# Nutrient_Management_Control.net
KiCad netlist of a schematic drawn in EAGLE
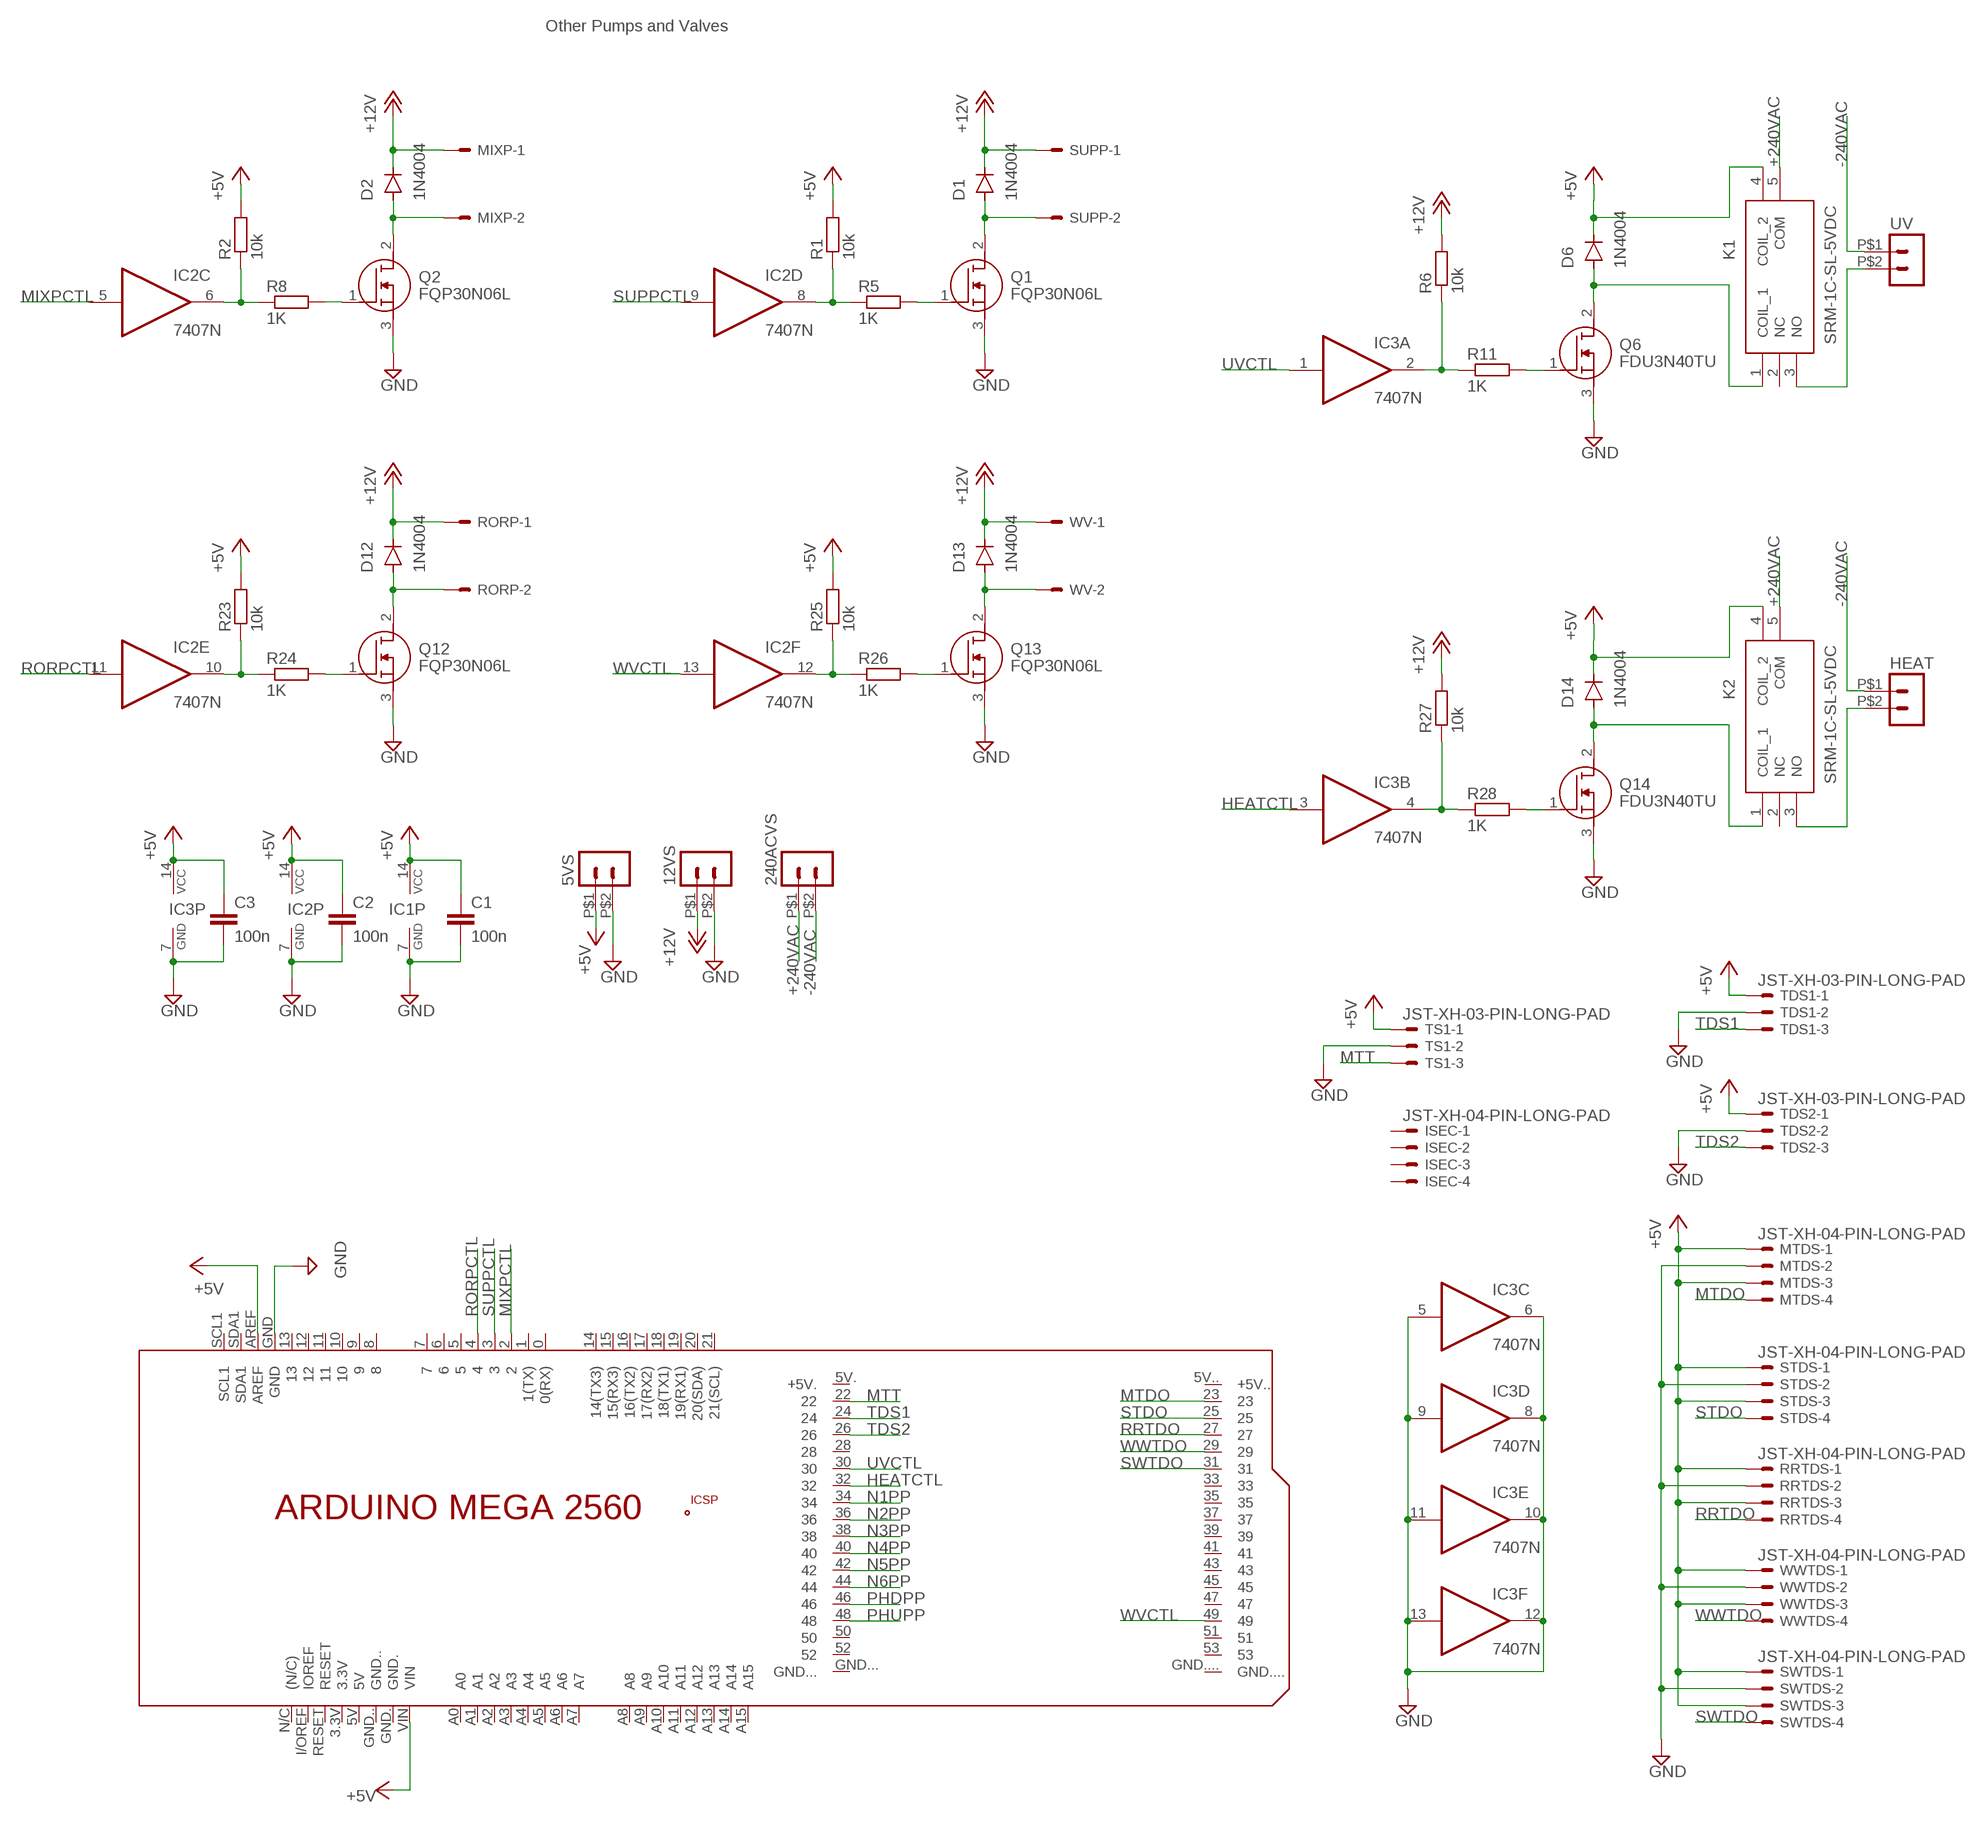
[diagram p0: schematic, sheet 1, part 1 of 2]
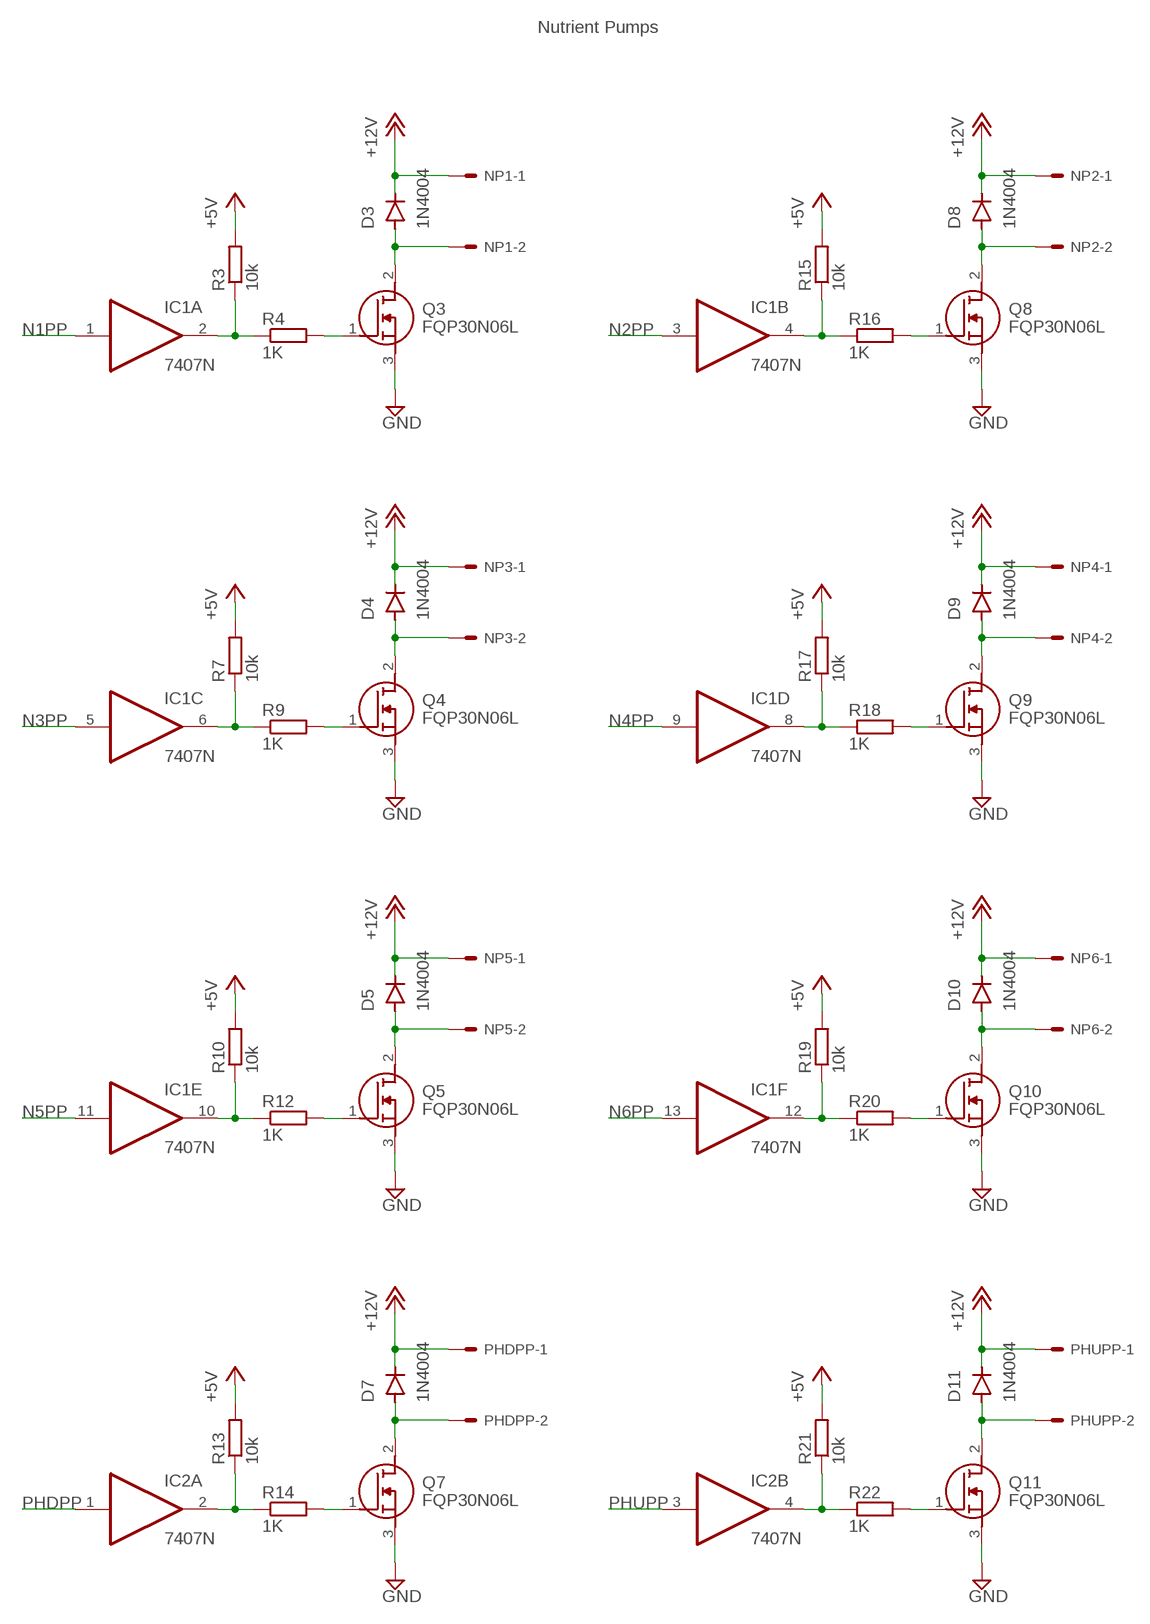
[diagram p1: schematic, sheet 1, part 2 of 2]

(export (version "E")
  (design (tool "Eeschema 10.0.6"))
  (components
    (comp (ref "5VS")
      (value "HEADER_POS2_43650-0215")
      (footprint "eagle-import:43650-0215")
      (libsource (lib "eagle-import") (part "HEADER_POS2_?43650-0215"))
    )
    (comp (ref "12VS")
      (value "HEADER_POS2_43650-0215")
      (footprint "eagle-import:43650-0215")
      (libsource (lib "eagle-import") (part "HEADER_POS2_?43650-0215"))
    )
    (comp (ref "240ACVS")
      (value "HEADER_POS2_43650-0215")
      (footprint "eagle-import:43650-0215")
      (libsource (lib "eagle-import") (part "HEADER_POS2_?43650-0215"))
    )
    (comp (ref "C1")
      (value "100n")
      (footprint "eagle-import:C050-024X044")
      (libsource (lib "eagle-import") (part "C-EU050-024X044"))
    )
    (comp (ref "C2")
      (value "100n")
      (footprint "eagle-import:C050-024X044")
      (libsource (lib "eagle-import") (part "C-EU050-024X044"))
    )
    (comp (ref "C3")
      (value "100n")
      (footprint "eagle-import:C050-024X044")
      (libsource (lib "eagle-import") (part "C-EU050-024X044"))
    )
    (comp (ref "D1")
      (value "1N4004")
      (footprint "eagle-import:DO-41")
      (fields
        (field (name "DIGIKEY_PART_NUMBER") "1N4004MSCT-ND")
        (field (name "MANUFACTURER") "Micro Commercial Co")
        (field (name "CREATED_BY") "PCBLayout.com")
      )
      (libsource (lib "eagle-import") (part "1N4004"))
    )
    (comp (ref "D2")
      (value "1N4004")
      (footprint "eagle-import:DO-41")
      (fields
        (field (name "DIGIKEY_PART_NUMBER") "1N4004MSCT-ND")
        (field (name "MANUFACTURER") "Micro Commercial Co")
        (field (name "CREATED_BY") "PCBLayout.com")
      )
      (libsource (lib "eagle-import") (part "1N4004"))
    )
    (comp (ref "D3")
      (value "1N4004")
      (footprint "eagle-import:DO-41")
      (fields
        (field (name "DIGIKEY_PART_NUMBER") "1N4004MSCT-ND")
        (field (name "MANUFACTURER") "Micro Commercial Co")
        (field (name "CREATED_BY") "PCBLayout.com")
      )
      (libsource (lib "eagle-import") (part "1N4004"))
    )
    (comp (ref "D4")
      (value "1N4004")
      (footprint "eagle-import:DO-41")
      (fields
        (field (name "DIGIKEY_PART_NUMBER") "1N4004MSCT-ND")
        (field (name "MANUFACTURER") "Micro Commercial Co")
        (field (name "CREATED_BY") "PCBLayout.com")
      )
      (libsource (lib "eagle-import") (part "1N4004"))
    )
    (comp (ref "D5")
      (value "1N4004")
      (footprint "eagle-import:DO-41")
      (fields
        (field (name "DIGIKEY_PART_NUMBER") "1N4004MSCT-ND")
        (field (name "MANUFACTURER") "Micro Commercial Co")
        (field (name "CREATED_BY") "PCBLayout.com")
      )
      (libsource (lib "eagle-import") (part "1N4004"))
    )
    (comp (ref "D6")
      (value "1N4004")
      (footprint "eagle-import:DO-41")
      (fields
        (field (name "DIGIKEY_PART_NUMBER") "1N4004MSCT-ND")
        (field (name "MANUFACTURER") "Micro Commercial Co")
        (field (name "CREATED_BY") "PCBLayout.com")
      )
      (libsource (lib "eagle-import") (part "1N4004"))
    )
    (comp (ref "D7")
      (value "1N4004")
      (footprint "eagle-import:DO-41")
      (fields
        (field (name "DIGIKEY_PART_NUMBER") "1N4004MSCT-ND")
        (field (name "MANUFACTURER") "Micro Commercial Co")
        (field (name "CREATED_BY") "PCBLayout.com")
      )
      (libsource (lib "eagle-import") (part "1N4004"))
    )
    (comp (ref "D8")
      (value "1N4004")
      (footprint "eagle-import:DO-41")
      (fields
        (field (name "DIGIKEY_PART_NUMBER") "1N4004MSCT-ND")
        (field (name "MANUFACTURER") "Micro Commercial Co")
        (field (name "CREATED_BY") "PCBLayout.com")
      )
      (libsource (lib "eagle-import") (part "1N4004"))
    )
    (comp (ref "D9")
      (value "1N4004")
      (footprint "eagle-import:DO-41")
      (fields
        (field (name "DIGIKEY_PART_NUMBER") "1N4004MSCT-ND")
        (field (name "MANUFACTURER") "Micro Commercial Co")
        (field (name "CREATED_BY") "PCBLayout.com")
      )
      (libsource (lib "eagle-import") (part "1N4004"))
    )
    (comp (ref "D10")
      (value "1N4004")
      (footprint "eagle-import:DO-41")
      (fields
        (field (name "DIGIKEY_PART_NUMBER") "1N4004MSCT-ND")
        (field (name "MANUFACTURER") "Micro Commercial Co")
        (field (name "CREATED_BY") "PCBLayout.com")
      )
      (libsource (lib "eagle-import") (part "1N4004"))
    )
    (comp (ref "D11")
      (value "1N4004")
      (footprint "eagle-import:DO-41")
      (fields
        (field (name "DIGIKEY_PART_NUMBER") "1N4004MSCT-ND")
        (field (name "MANUFACTURER") "Micro Commercial Co")
        (field (name "CREATED_BY") "PCBLayout.com")
      )
      (libsource (lib "eagle-import") (part "1N4004"))
    )
    (comp (ref "D12")
      (value "1N4004")
      (footprint "eagle-import:DO-41")
      (fields
        (field (name "DIGIKEY_PART_NUMBER") "1N4004MSCT-ND")
        (field (name "MANUFACTURER") "Micro Commercial Co")
        (field (name "CREATED_BY") "PCBLayout.com")
      )
      (libsource (lib "eagle-import") (part "1N4004"))
    )
    (comp (ref "D13")
      (value "1N4004")
      (footprint "eagle-import:DO-41")
      (fields
        (field (name "DIGIKEY_PART_NUMBER") "1N4004MSCT-ND")
        (field (name "MANUFACTURER") "Micro Commercial Co")
        (field (name "CREATED_BY") "PCBLayout.com")
      )
      (libsource (lib "eagle-import") (part "1N4004"))
    )
    (comp (ref "D14")
      (value "1N4004")
      (footprint "eagle-import:DO-41")
      (fields
        (field (name "DIGIKEY_PART_NUMBER") "1N4004MSCT-ND")
        (field (name "MANUFACTURER") "Micro Commercial Co")
        (field (name "CREATED_BY") "PCBLayout.com")
      )
      (libsource (lib "eagle-import") (part "1N4004"))
    )
    (comp (ref "HEAT")
      (value "HEADER_POS2_43650-0215")
      (footprint "eagle-import:43650-0215")
      (libsource (lib "eagle-import") (part "HEADER_POS2_?43650-0215"))
    )
    (comp (ref "IC1")
      (value "7407N")
      (footprint "eagle-import:DIL14")
      (libsource (lib "eagle-import") (part "7407N"))
    )
    (comp (ref "IC2")
      (value "7407N")
      (footprint "eagle-import:DIL14")
      (libsource (lib "eagle-import") (part "7407N"))
    )
    (comp (ref "IC3")
      (value "7407N")
      (footprint "eagle-import:DIL14")
      (libsource (lib "eagle-import") (part "7407N"))
    )
    (comp (ref "ISEC")
      (value "JST-XH-04-PIN-LONG-PAD")
      (footprint "eagle-import:JST-XH-04-PACKAGE-LONG-PAD")
      (libsource (lib "eagle-import") (part "JST-XH-04-PIN-LONG-PAD"))
    )
    (comp (ref "K1")
      (value "SRM-1C-SL-5VDC")
      (footprint "eagle-import:SRM1CSL5VDC")
      (libsource (lib "eagle-import") (part "SRM-1C-SL-5VDC"))
    )
    (comp (ref "K2")
      (value "SRM-1C-SL-5VDC")
      (footprint "eagle-import:SRM1CSL5VDC")
      (libsource (lib "eagle-import") (part "SRM-1C-SL-5VDC"))
    )
    (comp (ref "MIXP")
      (value "JST-XH-02-PIN-LONG-PAD")
      (footprint "eagle-import:JST-XH-02-PACKAGE-LONG-PAD")
      (libsource (lib "eagle-import") (part "JST-XH-02-PIN-LONG-PAD"))
    )
    (comp (ref "MTDS")
      (value "JST-XH-04-PIN-LONG-PAD")
      (footprint "eagle-import:JST-XH-04-PACKAGE-LONG-PAD")
      (libsource (lib "eagle-import") (part "JST-XH-04-PIN-LONG-PAD"))
    )
    (comp (ref "NP1")
      (value "JST-XH-02-PIN-LONG-PAD")
      (footprint "eagle-import:JST-XH-02-PACKAGE-LONG-PAD")
      (libsource (lib "eagle-import") (part "JST-XH-02-PIN-LONG-PAD"))
    )
    (comp (ref "NP2")
      (value "JST-XH-02-PIN-LONG-PAD")
      (footprint "eagle-import:JST-XH-02-PACKAGE-LONG-PAD")
      (libsource (lib "eagle-import") (part "JST-XH-02-PIN-LONG-PAD"))
    )
    (comp (ref "NP3")
      (value "JST-XH-02-PIN-LONG-PAD")
      (footprint "eagle-import:JST-XH-02-PACKAGE-LONG-PAD")
      (libsource (lib "eagle-import") (part "JST-XH-02-PIN-LONG-PAD"))
    )
    (comp (ref "NP4")
      (value "JST-XH-02-PIN-LONG-PAD")
      (footprint "eagle-import:JST-XH-02-PACKAGE-LONG-PAD")
      (libsource (lib "eagle-import") (part "JST-XH-02-PIN-LONG-PAD"))
    )
    (comp (ref "NP5")
      (value "JST-XH-02-PIN-LONG-PAD")
      (footprint "eagle-import:JST-XH-02-PACKAGE-LONG-PAD")
      (libsource (lib "eagle-import") (part "JST-XH-02-PIN-LONG-PAD"))
    )
    (comp (ref "NP6")
      (value "JST-XH-02-PIN-LONG-PAD")
      (footprint "eagle-import:JST-XH-02-PACKAGE-LONG-PAD")
      (libsource (lib "eagle-import") (part "JST-XH-02-PIN-LONG-PAD"))
    )
    (comp (ref "PCB2")
      (value "ARDUINO_MEGA2560_SHIELD")
      (footprint "eagle-import:ARDUINO_MEGA2560_SHIELD")
      (libsource (lib "eagle-import") (part "ARDUINO_MEGA2560_SHIELD"))
    )
    (comp (ref "PHDPP")
      (value "JST-XH-02-PIN-LONG-PAD")
      (footprint "eagle-import:JST-XH-02-PACKAGE-LONG-PAD")
      (libsource (lib "eagle-import") (part "JST-XH-02-PIN-LONG-PAD"))
    )
    (comp (ref "PHUPP")
      (value "JST-XH-02-PIN-LONG-PAD")
      (footprint "eagle-import:JST-XH-02-PACKAGE-LONG-PAD")
      (libsource (lib "eagle-import") (part "JST-XH-02-PIN-LONG-PAD"))
    )
    (comp (ref "Q1")
      (value "FQP30N06L")
      (footprint "eagle-import:TO254P470X1016X2019-3P")
      (fields (field (name "RS_PART_NUMBER") "8075863P"))
      (libsource (lib "eagle-import") (part "FQP30N06L"))
    )
    (comp (ref "Q2")
      (value "FQP30N06L")
      (footprint "eagle-import:TO254P470X1016X2019-3P")
      (fields (field (name "RS_PART_NUMBER") "8075863P"))
      (libsource (lib "eagle-import") (part "FQP30N06L"))
    )
    (comp (ref "Q3")
      (value "FQP30N06L")
      (footprint "eagle-import:TO254P470X1016X2019-3P")
      (fields (field (name "RS_PART_NUMBER") "8075863P"))
      (libsource (lib "eagle-import") (part "FQP30N06L"))
    )
    (comp (ref "Q4")
      (value "FQP30N06L")
      (footprint "eagle-import:TO254P470X1016X2019-3P")
      (fields (field (name "RS_PART_NUMBER") "8075863P"))
      (libsource (lib "eagle-import") (part "FQP30N06L"))
    )
    (comp (ref "Q5")
      (value "FQP30N06L")
      (footprint "eagle-import:TO254P470X1016X2019-3P")
      (fields (field (name "RS_PART_NUMBER") "8075863P"))
      (libsource (lib "eagle-import") (part "FQP30N06L"))
    )
    (comp (ref "Q6")
      (value "FDU3N40TU")
      (footprint "eagle-import:TO229P250X658X985-3P")
      (fields (field (name "RS_PART_NUMBER") "8070701P"))
      (libsource (lib "eagle-import") (part "FDU3N40TU"))
    )
    (comp (ref "Q7")
      (value "FQP30N06L")
      (footprint "eagle-import:TO254P470X1016X2019-3P")
      (fields (field (name "RS_PART_NUMBER") "8075863P"))
      (libsource (lib "eagle-import") (part "FQP30N06L"))
    )
    (comp (ref "Q8")
      (value "FQP30N06L")
      (footprint "eagle-import:TO254P470X1016X2019-3P")
      (fields (field (name "RS_PART_NUMBER") "8075863P"))
      (libsource (lib "eagle-import") (part "FQP30N06L"))
    )
    (comp (ref "Q9")
      (value "FQP30N06L")
      (footprint "eagle-import:TO254P470X1016X2019-3P")
      (fields (field (name "RS_PART_NUMBER") "8075863P"))
      (libsource (lib "eagle-import") (part "FQP30N06L"))
    )
    (comp (ref "Q10")
      (value "FQP30N06L")
      (footprint "eagle-import:TO254P470X1016X2019-3P")
      (fields (field (name "RS_PART_NUMBER") "8075863P"))
      (libsource (lib "eagle-import") (part "FQP30N06L"))
    )
    (comp (ref "Q11")
      (value "FQP30N06L")
      (footprint "eagle-import:TO254P470X1016X2019-3P")
      (fields (field (name "RS_PART_NUMBER") "8075863P"))
      (libsource (lib "eagle-import") (part "FQP30N06L"))
    )
    (comp (ref "Q12")
      (value "FQP30N06L")
      (footprint "eagle-import:TO254P470X1016X2019-3P")
      (fields (field (name "RS_PART_NUMBER") "8075863P"))
      (libsource (lib "eagle-import") (part "FQP30N06L"))
    )
    (comp (ref "Q13")
      (value "FQP30N06L")
      (footprint "eagle-import:TO254P470X1016X2019-3P")
      (fields (field (name "RS_PART_NUMBER") "8075863P"))
      (libsource (lib "eagle-import") (part "FQP30N06L"))
    )
    (comp (ref "Q14")
      (value "FDU3N40TU")
      (footprint "eagle-import:TO229P250X658X985-3P")
      (fields (field (name "RS_PART_NUMBER") "8070701P"))
      (libsource (lib "eagle-import") (part "FDU3N40TU"))
    )
    (comp (ref "R1")
      (value "10k")
      (footprint "eagle-import:0204_7")
      (libsource (lib "eagle-import") (part "R-EU_0204/7"))
    )
    (comp (ref "R2")
      (value "10k")
      (footprint "eagle-import:0204_7")
      (libsource (lib "eagle-import") (part "R-EU_0204/7"))
    )
    (comp (ref "R3")
      (value "10k")
      (footprint "eagle-import:0204_7")
      (libsource (lib "eagle-import") (part "R-EU_0204/7"))
    )
    (comp (ref "R4")
      (value "1K")
      (footprint "eagle-import:0204_7")
      (libsource (lib "eagle-import") (part "R-EU_0204/7"))
    )
    (comp (ref "R5")
      (value "1K")
      (footprint "eagle-import:0204_7")
      (libsource (lib "eagle-import") (part "R-EU_0204/7"))
    )
    (comp (ref "R6")
      (value "10k")
      (footprint "eagle-import:0204_7")
      (libsource (lib "eagle-import") (part "R-EU_0204/7"))
    )
    (comp (ref "R7")
      (value "10k")
      (footprint "eagle-import:0204_7")
      (libsource (lib "eagle-import") (part "R-EU_0204/7"))
    )
    (comp (ref "R8")
      (value "1K")
      (footprint "eagle-import:0204_7")
      (libsource (lib "eagle-import") (part "R-EU_0204/7"))
    )
    (comp (ref "R9")
      (value "1K")
      (footprint "eagle-import:0204_7")
      (libsource (lib "eagle-import") (part "R-EU_0204/7"))
    )
    (comp (ref "R10")
      (value "10k")
      (footprint "eagle-import:0204_7")
      (libsource (lib "eagle-import") (part "R-EU_0204/7"))
    )
    (comp (ref "R11")
      (value "1K")
      (footprint "eagle-import:0204_7")
      (libsource (lib "eagle-import") (part "R-EU_0204/7"))
    )
    (comp (ref "R12")
      (value "1K")
      (footprint "eagle-import:0204_7")
      (libsource (lib "eagle-import") (part "R-EU_0204/7"))
    )
    (comp (ref "R13")
      (value "10k")
      (footprint "eagle-import:0204_7")
      (libsource (lib "eagle-import") (part "R-EU_0204/7"))
    )
    (comp (ref "R14")
      (value "1K")
      (footprint "eagle-import:0204_7")
      (libsource (lib "eagle-import") (part "R-EU_0204/7"))
    )
    (comp (ref "R15")
      (value "10k")
      (footprint "eagle-import:0204_7")
      (libsource (lib "eagle-import") (part "R-EU_0204/7"))
    )
    (comp (ref "R16")
      (value "1K")
      (footprint "eagle-import:0204_7")
      (libsource (lib "eagle-import") (part "R-EU_0204/7"))
    )
    (comp (ref "R17")
      (value "10k")
      (footprint "eagle-import:0204_7")
      (libsource (lib "eagle-import") (part "R-EU_0204/7"))
    )
    (comp (ref "R18")
      (value "1K")
      (footprint "eagle-import:0204_7")
      (libsource (lib "eagle-import") (part "R-EU_0204/7"))
    )
    (comp (ref "R19")
      (value "10k")
      (footprint "eagle-import:0204_7")
      (libsource (lib "eagle-import") (part "R-EU_0204/7"))
    )
    (comp (ref "R20")
      (value "1K")
      (footprint "eagle-import:0204_7")
      (libsource (lib "eagle-import") (part "R-EU_0204/7"))
    )
    (comp (ref "R21")
      (value "10k")
      (footprint "eagle-import:0204_7")
      (libsource (lib "eagle-import") (part "R-EU_0204/7"))
    )
    (comp (ref "R22")
      (value "1K")
      (footprint "eagle-import:0204_7")
      (libsource (lib "eagle-import") (part "R-EU_0204/7"))
    )
    (comp (ref "R23")
      (value "10k")
      (footprint "eagle-import:0204_7")
      (libsource (lib "eagle-import") (part "R-EU_0204/7"))
    )
    (comp (ref "R24")
      (value "1K")
      (footprint "eagle-import:0204_7")
      (libsource (lib "eagle-import") (part "R-EU_0204/7"))
    )
    (comp (ref "R25")
      (value "10k")
      (footprint "eagle-import:0204_7")
      (libsource (lib "eagle-import") (part "R-EU_0204/7"))
    )
    (comp (ref "R26")
      (value "1K")
      (footprint "eagle-import:0204_7")
      (libsource (lib "eagle-import") (part "R-EU_0204/7"))
    )
    (comp (ref "R27")
      (value "10k")
      (footprint "eagle-import:0204_7")
      (libsource (lib "eagle-import") (part "R-EU_0204/7"))
    )
    (comp (ref "R28")
      (value "1K")
      (footprint "eagle-import:0204_7")
      (libsource (lib "eagle-import") (part "R-EU_0204/7"))
    )
    (comp (ref "RORP")
      (value "JST-XH-02-PIN-LONG-PAD")
      (footprint "eagle-import:JST-XH-02-PACKAGE-LONG-PAD")
      (libsource (lib "eagle-import") (part "JST-XH-02-PIN-LONG-PAD"))
    )
    (comp (ref "RRTDS")
      (value "JST-XH-04-PIN-LONG-PAD")
      (footprint "eagle-import:JST-XH-04-PACKAGE-LONG-PAD")
      (libsource (lib "eagle-import") (part "JST-XH-04-PIN-LONG-PAD"))
    )
    (comp (ref "STDS")
      (value "JST-XH-04-PIN-LONG-PAD")
      (footprint "eagle-import:JST-XH-04-PACKAGE-LONG-PAD")
      (libsource (lib "eagle-import") (part "JST-XH-04-PIN-LONG-PAD"))
    )
    (comp (ref "SUPP")
      (value "JST-XH-02-PIN-LONG-PAD")
      (footprint "eagle-import:JST-XH-02-PACKAGE-LONG-PAD")
      (libsource (lib "eagle-import") (part "JST-XH-02-PIN-LONG-PAD"))
    )
    (comp (ref "SWTDS")
      (value "JST-XH-04-PIN-LONG-PAD")
      (footprint "eagle-import:JST-XH-04-PACKAGE-LONG-PAD")
      (libsource (lib "eagle-import") (part "JST-XH-04-PIN-LONG-PAD"))
    )
    (comp (ref "TDS1")
      (value "JST-XH-03-PIN-LONG-PAD")
      (footprint "eagle-import:JST-XH-03-PACKAGE-LONG-PAD")
      (libsource (lib "eagle-import") (part "JST-XH-03-PIN-LONG-PAD"))
    )
    (comp (ref "TDS2")
      (value "JST-XH-03-PIN-LONG-PAD")
      (footprint "eagle-import:JST-XH-03-PACKAGE-LONG-PAD")
      (libsource (lib "eagle-import") (part "JST-XH-03-PIN-LONG-PAD"))
    )
    (comp (ref "TS1")
      (value "JST-XH-03-PIN-LONG-PAD")
      (footprint "eagle-import:JST-XH-03-PACKAGE-LONG-PAD")
      (libsource (lib "eagle-import") (part "JST-XH-03-PIN-LONG-PAD"))
    )
    (comp (ref "UV")
      (value "HEADER_POS2_43650-0215")
      (footprint "eagle-import:43650-0215")
      (libsource (lib "eagle-import") (part "HEADER_POS2_?43650-0215"))
    )
    (comp (ref "WV")
      (value "JST-XH-02-PIN-LONG-PAD")
      (footprint "eagle-import:JST-XH-02-PACKAGE-LONG-PAD")
      (libsource (lib "eagle-import") (part "JST-XH-02-PIN-LONG-PAD"))
    )
    (comp (ref "WWTDS")
      (value "JST-XH-04-PIN-LONG-PAD")
      (footprint "eagle-import:JST-XH-04-PACKAGE-LONG-PAD")
      (libsource (lib "eagle-import") (part "JST-XH-04-PIN-LONG-PAD"))
    )
  )
  (nets
    (net (code "1") (name "+5V") (class "Default")
      (node (ref "5VS") (pin "P$1") (pinfunction "1_P$1") (pintype "passive"))
      (node (ref "C1") (pin "1") (pinfunction "1_1") (pintype "passive"))
      (node (ref "C2") (pin "1") (pinfunction "1_1") (pintype "passive"))
      (node (ref "C3") (pin "1") (pinfunction "1_1") (pintype "passive"))
      (node (ref "D14") (pin "C") (pinfunction "C_C") (pintype "passive"))
      (node (ref "D6") (pin "C") (pinfunction "C_C") (pintype "passive"))
      (node (ref "IC1") (pin "14") (pinfunction "VCC_14") (pintype "power_in"))
      (node (ref "IC2") (pin "14") (pinfunction "VCC_14") (pintype "power_in"))
      (node (ref "IC3") (pin "14") (pinfunction "VCC_14") (pintype "power_in"))
      (node (ref "K1") (pin "4") (pinfunction "COIL_2_4") (pintype "bidirectional"))
      (node (ref "K2") (pin "4") (pinfunction "COIL_2_4") (pintype "bidirectional"))
      (node (ref "MTDS") (pin "1") (pinfunction "S_1") (pintype "passive"))
      (node (ref "MTDS") (pin "3") (pinfunction "S_3") (pintype "passive"))
      (node (ref "PCB2") (pin "AREF") (pinfunction "AREF_AREF") (pintype "bidirectional"))
      (node (ref "PCB2") (pin "VIN") (pinfunction "VIN_VIN") (pintype "bidirectional"))
      (node (ref "R1") (pin "2") (pinfunction "2_2") (pintype "passive"))
      (node (ref "R10") (pin "2") (pinfunction "2_2") (pintype "passive"))
      (node (ref "R13") (pin "2") (pinfunction "2_2") (pintype "passive"))
      (node (ref "R15") (pin "2") (pinfunction "2_2") (pintype "passive"))
      (node (ref "R17") (pin "2") (pinfunction "2_2") (pintype "passive"))
      (node (ref "R19") (pin "2") (pinfunction "2_2") (pintype "passive"))
      (node (ref "R2") (pin "2") (pinfunction "2_2") (pintype "passive"))
      (node (ref "R21") (pin "2") (pinfunction "2_2") (pintype "passive"))
      (node (ref "R23") (pin "2") (pinfunction "2_2") (pintype "passive"))
      (node (ref "R25") (pin "2") (pinfunction "2_2") (pintype "passive"))
      (node (ref "R3") (pin "2") (pinfunction "2_2") (pintype "passive"))
      (node (ref "R7") (pin "2") (pinfunction "2_2") (pintype "passive"))
      (node (ref "RRTDS") (pin "1") (pinfunction "S_1") (pintype "passive"))
      (node (ref "RRTDS") (pin "3") (pinfunction "S_3") (pintype "passive"))
      (node (ref "STDS") (pin "1") (pinfunction "S_1") (pintype "passive"))
      (node (ref "STDS") (pin "3") (pinfunction "S_3") (pintype "passive"))
      (node (ref "SWTDS") (pin "1") (pinfunction "S_1") (pintype "passive"))
      (node (ref "SWTDS") (pin "3") (pinfunction "S_3") (pintype "passive"))
      (node (ref "TDS1") (pin "1") (pinfunction "S_1") (pintype "passive"))
      (node (ref "TDS2") (pin "1") (pinfunction "S_1") (pintype "passive"))
      (node (ref "TS1") (pin "1") (pinfunction "S_1") (pintype "passive"))
      (node (ref "WWTDS") (pin "1") (pinfunction "S_1") (pintype "passive"))
      (node (ref "WWTDS") (pin "3") (pinfunction "S_3") (pintype "passive"))
    )
    (net (code "2") (name "+12V") (class "Default")
      (node (ref "12VS") (pin "P$1") (pinfunction "1_P$1") (pintype "passive"))
      (node (ref "D1") (pin "C") (pinfunction "C_C") (pintype "passive"))
      (node (ref "D10") (pin "C") (pinfunction "C_C") (pintype "passive"))
      (node (ref "D11") (pin "C") (pinfunction "C_C") (pintype "passive"))
      (node (ref "D12") (pin "C") (pinfunction "C_C") (pintype "passive"))
      (node (ref "D13") (pin "C") (pinfunction "C_C") (pintype "passive"))
      (node (ref "D2") (pin "C") (pinfunction "C_C") (pintype "passive"))
      (node (ref "D3") (pin "C") (pinfunction "C_C") (pintype "passive"))
      (node (ref "D4") (pin "C") (pinfunction "C_C") (pintype "passive"))
      (node (ref "D5") (pin "C") (pinfunction "C_C") (pintype "passive"))
      (node (ref "D7") (pin "C") (pinfunction "C_C") (pintype "passive"))
      (node (ref "D8") (pin "C") (pinfunction "C_C") (pintype "passive"))
      (node (ref "D9") (pin "C") (pinfunction "C_C") (pintype "passive"))
      (node (ref "MIXP") (pin "1") (pinfunction "S_1") (pintype "passive"))
      (node (ref "NP1") (pin "1") (pinfunction "S_1") (pintype "passive"))
      (node (ref "NP2") (pin "1") (pinfunction "S_1") (pintype "passive"))
      (node (ref "NP3") (pin "1") (pinfunction "S_1") (pintype "passive"))
      (node (ref "NP4") (pin "1") (pinfunction "S_1") (pintype "passive"))
      (node (ref "NP5") (pin "1") (pinfunction "S_1") (pintype "passive"))
      (node (ref "NP6") (pin "1") (pinfunction "S_1") (pintype "passive"))
      (node (ref "PHDPP") (pin "1") (pinfunction "S_1") (pintype "passive"))
      (node (ref "PHUPP") (pin "1") (pinfunction "S_1") (pintype "passive"))
      (node (ref "R27") (pin "2") (pinfunction "2_2") (pintype "passive"))
      (node (ref "R6") (pin "2") (pinfunction "2_2") (pintype "passive"))
      (node (ref "RORP") (pin "1") (pinfunction "S_1") (pintype "passive"))
      (node (ref "SUPP") (pin "1") (pinfunction "S_1") (pintype "passive"))
      (node (ref "WV") (pin "1") (pinfunction "S_1") (pintype "passive"))
    )
    (net (code "3") (name "/+240VAC") (class "Default")
      (node (ref "240ACVS") (pin "P$1") (pinfunction "1_P$1") (pintype "passive"))
      (node (ref "K1") (pin "5") (pinfunction "COM_5") (pintype "bidirectional"))
      (node (ref "K2") (pin "5") (pinfunction "COM_5") (pintype "bidirectional"))
    )
    (net (code "4") (name "/-240VAC") (class "Default")
      (node (ref "240ACVS") (pin "P$2") (pinfunction "2_P$2") (pintype "passive"))
      (node (ref "HEAT") (pin "P$1") (pinfunction "1_P$1") (pintype "passive"))
      (node (ref "UV") (pin "P$1") (pinfunction "1_P$1") (pintype "passive"))
    )
    (net (code "5") (name "/HEATCTL") (class "Default")
      (node (ref "IC3") (pin "3") (pinfunction "I_3") (pintype "input"))
      (node (ref "PCB2") (pin "32") (pinfunction "32_32") (pintype "bidirectional"))
    )
    (net (code "6") (name "/MIXPCTL") (class "Default")
      (node (ref "IC2") (pin "5") (pinfunction "I_5") (pintype "input"))
      (node (ref "PCB2") (pin "2") (pinfunction "2_2") (pintype "bidirectional"))
    )
    (net (code "7") (name "/MTDO") (class "Default")
      (node (ref "MTDS") (pin "4") (pinfunction "S_4") (pintype "passive"))
      (node (ref "PCB2") (pin "23") (pinfunction "23_23") (pintype "bidirectional"))
    )
    (net (code "8") (name "/MTT") (class "Default")
      (node (ref "PCB2") (pin "22") (pinfunction "22_22") (pintype "bidirectional"))
      (node (ref "TS1") (pin "3") (pinfunction "S_3") (pintype "passive"))
    )
    (net (code "9") (name "/N1PP") (class "Default")
      (node (ref "IC1") (pin "1") (pinfunction "I_1") (pintype "input"))
      (node (ref "PCB2") (pin "34") (pinfunction "34_34") (pintype "bidirectional"))
    )
    (net (code "10") (name "/N2PP") (class "Default")
      (node (ref "IC1") (pin "3") (pinfunction "I_3") (pintype "input"))
      (node (ref "PCB2") (pin "36") (pinfunction "36_36") (pintype "bidirectional"))
    )
    (net (code "11") (name "/N3PP") (class "Default")
      (node (ref "IC1") (pin "5") (pinfunction "I_5") (pintype "input"))
      (node (ref "PCB2") (pin "38") (pinfunction "38_38") (pintype "bidirectional"))
    )
    (net (code "12") (name "/N4PP") (class "Default")
      (node (ref "IC1") (pin "9") (pinfunction "I_9") (pintype "input"))
      (node (ref "PCB2") (pin "40") (pinfunction "40_40") (pintype "bidirectional"))
    )
    (net (code "13") (name "/N5PP") (class "Default")
      (node (ref "IC1") (pin "11") (pinfunction "I_11") (pintype "input"))
      (node (ref "PCB2") (pin "42") (pinfunction "42_42") (pintype "bidirectional"))
    )
    (net (code "14") (name "/N6PP") (class "Default")
      (node (ref "IC1") (pin "13") (pinfunction "I_13") (pintype "input"))
      (node (ref "PCB2") (pin "44") (pinfunction "44_44") (pintype "bidirectional"))
    )
    (net (code "15") (name "/PHDPP") (class "Default")
      (node (ref "IC2") (pin "1") (pinfunction "I_1") (pintype "input"))
      (node (ref "PCB2") (pin "46") (pinfunction "46_46") (pintype "bidirectional"))
    )
    (net (code "16") (name "/PHUPP") (class "Default")
      (node (ref "IC2") (pin "3") (pinfunction "I_3") (pintype "input"))
      (node (ref "PCB2") (pin "48") (pinfunction "48_48") (pintype "bidirectional"))
    )
    (net (code "17") (name "/RORPCTL") (class "Default")
      (node (ref "IC2") (pin "11") (pinfunction "I_11") (pintype "input"))
      (node (ref "PCB2") (pin "4") (pinfunction "4_4") (pintype "bidirectional"))
    )
    (net (code "18") (name "/RRTDO") (class "Default")
      (node (ref "PCB2") (pin "27") (pinfunction "27_27") (pintype "bidirectional"))
      (node (ref "RRTDS") (pin "4") (pinfunction "S_4") (pintype "passive"))
    )
    (net (code "19") (name "/STDO") (class "Default")
      (node (ref "PCB2") (pin "25") (pinfunction "25_25") (pintype "bidirectional"))
      (node (ref "STDS") (pin "4") (pinfunction "S_4") (pintype "passive"))
    )
    (net (code "20") (name "/SUPPCTL") (class "Default")
      (node (ref "IC2") (pin "9") (pinfunction "I_9") (pintype "input"))
      (node (ref "PCB2") (pin "3") (pinfunction "3_3") (pintype "bidirectional"))
    )
    (net (code "21") (name "/SWTDO") (class "Default")
      (node (ref "PCB2") (pin "31") (pinfunction "31_31") (pintype "bidirectional"))
      (node (ref "SWTDS") (pin "4") (pinfunction "S_4") (pintype "passive"))
    )
    (net (code "22") (name "/TDS1") (class "Default")
      (node (ref "PCB2") (pin "24") (pinfunction "24_24") (pintype "bidirectional"))
      (node (ref "TDS1") (pin "3") (pinfunction "S_3") (pintype "passive"))
    )
    (net (code "23") (name "/TDS2") (class "Default")
      (node (ref "PCB2") (pin "26") (pinfunction "26_26") (pintype "bidirectional"))
      (node (ref "TDS2") (pin "3") (pinfunction "S_3") (pintype "passive"))
    )
    (net (code "24") (name "/UVCTL") (class "Default")
      (node (ref "IC3") (pin "1") (pinfunction "I_1") (pintype "input"))
      (node (ref "PCB2") (pin "30") (pinfunction "30_30") (pintype "bidirectional"))
    )
    (net (code "25") (name "/WVCTL") (class "Default")
      (node (ref "IC2") (pin "13") (pinfunction "I_13") (pintype "input"))
      (node (ref "PCB2") (pin "49") (pinfunction "49_49") (pintype "bidirectional"))
    )
    (net (code "26") (name "/WWTDO") (class "Default")
      (node (ref "PCB2") (pin "29") (pinfunction "29_29") (pintype "bidirectional"))
      (node (ref "WWTDS") (pin "4") (pinfunction "S_4") (pintype "passive"))
    )
    (net (code "27") (name "GND") (class "Default")
      (node (ref "12VS") (pin "P$2") (pinfunction "2_P$2") (pintype "passive"))
      (node (ref "5VS") (pin "P$2") (pinfunction "2_P$2") (pintype "passive"))
      (node (ref "C1") (pin "2") (pinfunction "2_2") (pintype "passive"))
      (node (ref "C2") (pin "2") (pinfunction "2_2") (pintype "passive"))
      (node (ref "C3") (pin "2") (pinfunction "2_2") (pintype "passive"))
      (node (ref "IC1") (pin "7") (pinfunction "GND_7") (pintype "power_in"))
      (node (ref "IC2") (pin "7") (pinfunction "GND_7") (pintype "power_in"))
      (node (ref "IC3") (pin "10") (pinfunction "O_10") (pintype "open_collector"))
      (node (ref "IC3") (pin "11") (pinfunction "I_11") (pintype "input"))
      (node (ref "IC3") (pin "12") (pinfunction "O_12") (pintype "open_collector"))
      (node (ref "IC3") (pin "13") (pinfunction "I_13") (pintype "input"))
      (node (ref "IC3") (pin "5") (pinfunction "I_5") (pintype "input"))
      (node (ref "IC3") (pin "6") (pinfunction "O_6") (pintype "open_collector"))
      (node (ref "IC3") (pin "7") (pinfunction "GND_7") (pintype "power_in"))
      (node (ref "IC3") (pin "8") (pinfunction "O_8") (pintype "open_collector"))
      (node (ref "IC3") (pin "9") (pinfunction "I_9") (pintype "input"))
      (node (ref "MTDS") (pin "2") (pinfunction "S_2") (pintype "passive"))
      (node (ref "PCB2") (pin "GND") (pinfunction "GND_GND") (pintype "bidirectional"))
      (node (ref "Q1") (pin "3") (pinfunction "S_3") (pintype "bidirectional"))
      (node (ref "Q10") (pin "3") (pinfunction "S_3") (pintype "bidirectional"))
      (node (ref "Q11") (pin "3") (pinfunction "S_3") (pintype "bidirectional"))
      (node (ref "Q12") (pin "3") (pinfunction "S_3") (pintype "bidirectional"))
      (node (ref "Q13") (pin "3") (pinfunction "S_3") (pintype "bidirectional"))
      (node (ref "Q14") (pin "3") (pinfunction "S_3") (pintype "bidirectional"))
      (node (ref "Q2") (pin "3") (pinfunction "S_3") (pintype "bidirectional"))
      (node (ref "Q3") (pin "3") (pinfunction "S_3") (pintype "bidirectional"))
      (node (ref "Q4") (pin "3") (pinfunction "S_3") (pintype "bidirectional"))
      (node (ref "Q5") (pin "3") (pinfunction "S_3") (pintype "bidirectional"))
      (node (ref "Q6") (pin "3") (pinfunction "S_3") (pintype "bidirectional"))
      (node (ref "Q7") (pin "3") (pinfunction "S_3") (pintype "bidirectional"))
      (node (ref "Q8") (pin "3") (pinfunction "S_3") (pintype "bidirectional"))
      (node (ref "Q9") (pin "3") (pinfunction "S_3") (pintype "bidirectional"))
      (node (ref "RRTDS") (pin "2") (pinfunction "S_2") (pintype "passive"))
      (node (ref "STDS") (pin "2") (pinfunction "S_2") (pintype "passive"))
      (node (ref "SWTDS") (pin "2") (pinfunction "S_2") (pintype "passive"))
      (node (ref "TDS1") (pin "2") (pinfunction "S_2") (pintype "passive"))
      (node (ref "TDS2") (pin "2") (pinfunction "S_2") (pintype "passive"))
      (node (ref "TS1") (pin "2") (pinfunction "S_2") (pintype "passive"))
      (node (ref "WWTDS") (pin "2") (pinfunction "S_2") (pintype "passive"))
    )
    (net (code "28") (name "Net-(HEAT-2)") (class "Default")
      (node (ref "HEAT") (pin "P$2") (pinfunction "2_P$2") (pintype "passive"))
      (node (ref "K2") (pin "3") (pinfunction "NO_3") (pintype "bidirectional"))
    )
    (net (code "29") (name "Net-(IC1A-O)") (class "Default")
      (node (ref "IC1") (pin "2") (pinfunction "O_2") (pintype "open_collector"))
      (node (ref "R3") (pin "1") (pinfunction "1_1") (pintype "passive"))
      (node (ref "R4") (pin "1") (pinfunction "1_1") (pintype "passive"))
    )
    (net (code "30") (name "Net-(IC1B-O)") (class "Default")
      (node (ref "IC1") (pin "4") (pinfunction "O_4") (pintype "open_collector"))
      (node (ref "R15") (pin "1") (pinfunction "1_1") (pintype "passive"))
      (node (ref "R16") (pin "1") (pinfunction "1_1") (pintype "passive"))
    )
    (net (code "31") (name "Net-(IC1C-O)") (class "Default")
      (node (ref "IC1") (pin "6") (pinfunction "O_6") (pintype "open_collector"))
      (node (ref "R7") (pin "1") (pinfunction "1_1") (pintype "passive"))
      (node (ref "R9") (pin "1") (pinfunction "1_1") (pintype "passive"))
    )
    (net (code "32") (name "Net-(IC1D-O)") (class "Default")
      (node (ref "IC1") (pin "8") (pinfunction "O_8") (pintype "open_collector"))
      (node (ref "R17") (pin "1") (pinfunction "1_1") (pintype "passive"))
      (node (ref "R18") (pin "1") (pinfunction "1_1") (pintype "passive"))
    )
    (net (code "33") (name "Net-(IC1E-O)") (class "Default")
      (node (ref "IC1") (pin "10") (pinfunction "O_10") (pintype "open_collector"))
      (node (ref "R10") (pin "1") (pinfunction "1_1") (pintype "passive"))
      (node (ref "R12") (pin "1") (pinfunction "1_1") (pintype "passive"))
    )
    (net (code "34") (name "Net-(IC1F-O)") (class "Default")
      (node (ref "IC1") (pin "12") (pinfunction "O_12") (pintype "open_collector"))
      (node (ref "R19") (pin "1") (pinfunction "1_1") (pintype "passive"))
      (node (ref "R20") (pin "1") (pinfunction "1_1") (pintype "passive"))
    )
    (net (code "35") (name "Net-(IC2A-O)") (class "Default")
      (node (ref "IC2") (pin "2") (pinfunction "O_2") (pintype "open_collector"))
      (node (ref "R13") (pin "1") (pinfunction "1_1") (pintype "passive"))
      (node (ref "R14") (pin "1") (pinfunction "1_1") (pintype "passive"))
    )
    (net (code "36") (name "Net-(IC2B-O)") (class "Default")
      (node (ref "IC2") (pin "4") (pinfunction "O_4") (pintype "open_collector"))
      (node (ref "R21") (pin "1") (pinfunction "1_1") (pintype "passive"))
      (node (ref "R22") (pin "1") (pinfunction "1_1") (pintype "passive"))
    )
    (net (code "37") (name "Net-(IC2C-O)") (class "Default")
      (node (ref "IC2") (pin "6") (pinfunction "O_6") (pintype "open_collector"))
      (node (ref "R2") (pin "1") (pinfunction "1_1") (pintype "passive"))
      (node (ref "R8") (pin "1") (pinfunction "1_1") (pintype "passive"))
    )
    (net (code "38") (name "Net-(IC2D-O)") (class "Default")
      (node (ref "IC2") (pin "8") (pinfunction "O_8") (pintype "open_collector"))
      (node (ref "R1") (pin "1") (pinfunction "1_1") (pintype "passive"))
      (node (ref "R5") (pin "1") (pinfunction "1_1") (pintype "passive"))
    )
    (net (code "39") (name "Net-(IC2E-O)") (class "Default")
      (node (ref "IC2") (pin "10") (pinfunction "O_10") (pintype "open_collector"))
      (node (ref "R23") (pin "1") (pinfunction "1_1") (pintype "passive"))
      (node (ref "R24") (pin "1") (pinfunction "1_1") (pintype "passive"))
    )
    (net (code "40") (name "Net-(IC2F-O)") (class "Default")
      (node (ref "IC2") (pin "12") (pinfunction "O_12") (pintype "open_collector"))
      (node (ref "R25") (pin "1") (pinfunction "1_1") (pintype "passive"))
      (node (ref "R26") (pin "1") (pinfunction "1_1") (pintype "passive"))
    )
    (net (code "41") (name "Net-(IC3A-O)") (class "Default")
      (node (ref "IC3") (pin "2") (pinfunction "O_2") (pintype "open_collector"))
      (node (ref "R11") (pin "1") (pinfunction "1_1") (pintype "passive"))
      (node (ref "R6") (pin "1") (pinfunction "1_1") (pintype "passive"))
    )
    (net (code "42") (name "Net-(IC3B-O)") (class "Default")
      (node (ref "IC3") (pin "4") (pinfunction "O_4") (pintype "open_collector"))
      (node (ref "R27") (pin "1") (pinfunction "1_1") (pintype "passive"))
      (node (ref "R28") (pin "1") (pinfunction "1_1") (pintype "passive"))
    )
    (net (code "43") (name "Net-(K1-COIL_1)") (class "Default")
      (node (ref "D6") (pin "A") (pinfunction "A_A") (pintype "passive"))
      (node (ref "K1") (pin "1") (pinfunction "COIL_1_1") (pintype "bidirectional"))
      (node (ref "Q6") (pin "2") (pinfunction "D_2") (pintype "bidirectional"))
    )
    (net (code "44") (name "Net-(K1-NO)") (class "Default")
      (node (ref "K1") (pin "3") (pinfunction "NO_3") (pintype "bidirectional"))
      (node (ref "UV") (pin "P$2") (pinfunction "2_P$2") (pintype "passive"))
    )
    (net (code "45") (name "Net-(K2-COIL_1)") (class "Default")
      (node (ref "D14") (pin "A") (pinfunction "A_A") (pintype "passive"))
      (node (ref "K2") (pin "1") (pinfunction "COIL_1_1") (pintype "bidirectional"))
      (node (ref "Q14") (pin "2") (pinfunction "D_2") (pintype "bidirectional"))
    )
    (net (code "46") (name "Net-(MIXPB-S)") (class "Default")
      (node (ref "D2") (pin "A") (pinfunction "A_A") (pintype "passive"))
      (node (ref "MIXP") (pin "2") (pinfunction "S_2") (pintype "passive"))
      (node (ref "Q2") (pin "2") (pinfunction "D_2") (pintype "bidirectional"))
    )
    (net (code "47") (name "Net-(NP1B-S)") (class "Default")
      (node (ref "D3") (pin "A") (pinfunction "A_A") (pintype "passive"))
      (node (ref "NP1") (pin "2") (pinfunction "S_2") (pintype "passive"))
      (node (ref "Q3") (pin "2") (pinfunction "D_2") (pintype "bidirectional"))
    )
    (net (code "48") (name "Net-(NP2B-S)") (class "Default")
      (node (ref "D8") (pin "A") (pinfunction "A_A") (pintype "passive"))
      (node (ref "NP2") (pin "2") (pinfunction "S_2") (pintype "passive"))
      (node (ref "Q8") (pin "2") (pinfunction "D_2") (pintype "bidirectional"))
    )
    (net (code "49") (name "Net-(NP3B-S)") (class "Default")
      (node (ref "D4") (pin "A") (pinfunction "A_A") (pintype "passive"))
      (node (ref "NP3") (pin "2") (pinfunction "S_2") (pintype "passive"))
      (node (ref "Q4") (pin "2") (pinfunction "D_2") (pintype "bidirectional"))
    )
    (net (code "50") (name "Net-(NP4B-S)") (class "Default")
      (node (ref "D9") (pin "A") (pinfunction "A_A") (pintype "passive"))
      (node (ref "NP4") (pin "2") (pinfunction "S_2") (pintype "passive"))
      (node (ref "Q9") (pin "2") (pinfunction "D_2") (pintype "bidirectional"))
    )
    (net (code "51") (name "Net-(NP5B-S)") (class "Default")
      (node (ref "D5") (pin "A") (pinfunction "A_A") (pintype "passive"))
      (node (ref "NP5") (pin "2") (pinfunction "S_2") (pintype "passive"))
      (node (ref "Q5") (pin "2") (pinfunction "D_2") (pintype "bidirectional"))
    )
    (net (code "52") (name "Net-(NP6B-S)") (class "Default")
      (node (ref "D10") (pin "A") (pinfunction "A_A") (pintype "passive"))
      (node (ref "NP6") (pin "2") (pinfunction "S_2") (pintype "passive"))
      (node (ref "Q10") (pin "2") (pinfunction "D_2") (pintype "bidirectional"))
    )
    (net (code "53") (name "Net-(PHDPPB-S)") (class "Default")
      (node (ref "D7") (pin "A") (pinfunction "A_A") (pintype "passive"))
      (node (ref "PHDPP") (pin "2") (pinfunction "S_2") (pintype "passive"))
      (node (ref "Q7") (pin "2") (pinfunction "D_2") (pintype "bidirectional"))
    )
    (net (code "54") (name "Net-(PHUPPB-S)") (class "Default")
      (node (ref "D11") (pin "A") (pinfunction "A_A") (pintype "passive"))
      (node (ref "PHUPP") (pin "2") (pinfunction "S_2") (pintype "passive"))
      (node (ref "Q11") (pin "2") (pinfunction "D_2") (pintype "bidirectional"))
    )
    (net (code "55") (name "Net-(Q1-D)") (class "Default")
      (node (ref "D1") (pin "A") (pinfunction "A_A") (pintype "passive"))
      (node (ref "Q1") (pin "2") (pinfunction "D_2") (pintype "bidirectional"))
      (node (ref "SUPP") (pin "2") (pinfunction "S_2") (pintype "passive"))
    )
    (net (code "56") (name "Net-(Q1-G)") (class "Default")
      (node (ref "Q1") (pin "1") (pinfunction "G_1") (pintype "bidirectional"))
      (node (ref "R5") (pin "2") (pinfunction "2_2") (pintype "passive"))
    )
    (net (code "57") (name "Net-(Q2-G)") (class "Default")
      (node (ref "Q2") (pin "1") (pinfunction "G_1") (pintype "bidirectional"))
      (node (ref "R8") (pin "2") (pinfunction "2_2") (pintype "passive"))
    )
    (net (code "58") (name "Net-(Q3-G)") (class "Default")
      (node (ref "Q3") (pin "1") (pinfunction "G_1") (pintype "bidirectional"))
      (node (ref "R4") (pin "2") (pinfunction "2_2") (pintype "passive"))
    )
    (net (code "59") (name "Net-(Q4-G)") (class "Default")
      (node (ref "Q4") (pin "1") (pinfunction "G_1") (pintype "bidirectional"))
      (node (ref "R9") (pin "2") (pinfunction "2_2") (pintype "passive"))
    )
    (net (code "60") (name "Net-(Q5-G)") (class "Default")
      (node (ref "Q5") (pin "1") (pinfunction "G_1") (pintype "bidirectional"))
      (node (ref "R12") (pin "2") (pinfunction "2_2") (pintype "passive"))
    )
    (net (code "61") (name "Net-(Q6-G)") (class "Default")
      (node (ref "Q6") (pin "1") (pinfunction "G_1") (pintype "bidirectional"))
      (node (ref "R11") (pin "2") (pinfunction "2_2") (pintype "passive"))
    )
    (net (code "62") (name "Net-(Q7-G)") (class "Default")
      (node (ref "Q7") (pin "1") (pinfunction "G_1") (pintype "bidirectional"))
      (node (ref "R14") (pin "2") (pinfunction "2_2") (pintype "passive"))
    )
    (net (code "63") (name "Net-(Q8-G)") (class "Default")
      (node (ref "Q8") (pin "1") (pinfunction "G_1") (pintype "bidirectional"))
      (node (ref "R16") (pin "2") (pinfunction "2_2") (pintype "passive"))
    )
    (net (code "64") (name "Net-(Q9-G)") (class "Default")
      (node (ref "Q9") (pin "1") (pinfunction "G_1") (pintype "bidirectional"))
      (node (ref "R18") (pin "2") (pinfunction "2_2") (pintype "passive"))
    )
    (net (code "65") (name "Net-(Q10-G)") (class "Default")
      (node (ref "Q10") (pin "1") (pinfunction "G_1") (pintype "bidirectional"))
      (node (ref "R20") (pin "2") (pinfunction "2_2") (pintype "passive"))
    )
    (net (code "66") (name "Net-(Q11-G)") (class "Default")
      (node (ref "Q11") (pin "1") (pinfunction "G_1") (pintype "bidirectional"))
      (node (ref "R22") (pin "2") (pinfunction "2_2") (pintype "passive"))
    )
    (net (code "67") (name "Net-(Q12-D)") (class "Default")
      (node (ref "D12") (pin "A") (pinfunction "A_A") (pintype "passive"))
      (node (ref "Q12") (pin "2") (pinfunction "D_2") (pintype "bidirectional"))
      (node (ref "RORP") (pin "2") (pinfunction "S_2") (pintype "passive"))
    )
    (net (code "68") (name "Net-(Q12-G)") (class "Default")
      (node (ref "Q12") (pin "1") (pinfunction "G_1") (pintype "bidirectional"))
      (node (ref "R24") (pin "2") (pinfunction "2_2") (pintype "passive"))
    )
    (net (code "69") (name "Net-(Q13-D)") (class "Default")
      (node (ref "D13") (pin "A") (pinfunction "A_A") (pintype "passive"))
      (node (ref "Q13") (pin "2") (pinfunction "D_2") (pintype "bidirectional"))
      (node (ref "WV") (pin "2") (pinfunction "S_2") (pintype "passive"))
    )
    (net (code "70") (name "Net-(Q13-G)") (class "Default")
      (node (ref "Q13") (pin "1") (pinfunction "G_1") (pintype "bidirectional"))
      (node (ref "R26") (pin "2") (pinfunction "2_2") (pintype "passive"))
    )
    (net (code "71") (name "Net-(Q14-G)") (class "Default")
      (node (ref "Q14") (pin "1") (pinfunction "G_1") (pintype "bidirectional"))
      (node (ref "R28") (pin "2") (pinfunction "2_2") (pintype "passive"))
    )
    (net (code "72") (name "unconnected-(ISECA-S-Pad1)") (class "Default")
      (node (ref "ISEC") (pin "1") (pinfunction "S_1") (pintype "passive"))
    )
    (net (code "73") (name "unconnected-(ISECB-S-Pad2)") (class "Default")
      (node (ref "ISEC") (pin "2") (pinfunction "S_2") (pintype "passive"))
    )
    (net (code "74") (name "unconnected-(ISECC-S-Pad3)") (class "Default")
      (node (ref "ISEC") (pin "3") (pinfunction "S_3") (pintype "passive"))
    )
    (net (code "75") (name "unconnected-(ISECD-S-Pad4)") (class "Default")
      (node (ref "ISEC") (pin "4") (pinfunction "S_4") (pintype "passive"))
    )
    (net (code "76") (name "unconnected-(K1-NC-Pad2)") (class "Default")
      (node (ref "K1") (pin "2") (pinfunction "NC_2") (pintype "no_connect"))
    )
    (net (code "77") (name "unconnected-(K2-NC-Pad2)") (class "Default")
      (node (ref "K2") (pin "2") (pinfunction "NC_2") (pintype "no_connect"))
    )
    (net (code "78") (name "unconnected-(PCB2-(N{slash}C)-PadN{slash}C)") (class "Default")
      (node (ref "PCB2") (pin "N/C") (pinfunction "(N/C)_N/C") (pintype "bidirectional"))
    )
    (net (code "79") (name "unconnected-(PCB2-+5V.-Pad5V.)") (class "Default")
      (node (ref "PCB2") (pin "5V.") (pinfunction "+5V._5V.") (pintype "bidirectional"))
    )
    (net (code "80") (name "unconnected-(PCB2-+5V..-Pad5V..)") (class "Default")
      (node (ref "PCB2") (pin "5V..") (pinfunction "+5V.._5V..") (pintype "bidirectional"))
    )
    (net (code "81") (name "unconnected-(PCB2-0(RX)-Pad0)") (class "Default")
      (node (ref "PCB2") (pin "0") (pinfunction "0(RX)_0") (pintype "bidirectional"))
    )
    (net (code "82") (name "unconnected-(PCB2-1(TX)-Pad1)") (class "Default")
      (node (ref "PCB2") (pin "1") (pinfunction "1(TX)_1") (pintype "bidirectional"))
    )
    (net (code "83") (name "unconnected-(PCB2-14(TX3)-Pad14)") (class "Default")
      (node (ref "PCB2") (pin "14") (pinfunction "14(TX3)_14") (pintype "bidirectional"))
    )
    (net (code "84") (name "unconnected-(PCB2-15(RX3)-Pad15)") (class "Default")
      (node (ref "PCB2") (pin "15") (pinfunction "15(RX3)_15") (pintype "bidirectional"))
    )
    (net (code "85") (name "unconnected-(PCB2-16(TX2)-Pad16)") (class "Default")
      (node (ref "PCB2") (pin "16") (pinfunction "16(TX2)_16") (pintype "bidirectional"))
    )
    (net (code "86") (name "unconnected-(PCB2-17(RX2)-Pad17)") (class "Default")
      (node (ref "PCB2") (pin "17") (pinfunction "17(RX2)_17") (pintype "bidirectional"))
    )
    (net (code "87") (name "unconnected-(PCB2-18(TX1)-Pad18)") (class "Default")
      (node (ref "PCB2") (pin "18") (pinfunction "18(TX1)_18") (pintype "bidirectional"))
    )
    (net (code "88") (name "unconnected-(PCB2-19(RX1)-Pad19)") (class "Default")
      (node (ref "PCB2") (pin "19") (pinfunction "19(RX1)_19") (pintype "bidirectional"))
    )
    (net (code "89") (name "unconnected-(PCB2-20(SDA)-Pad20)") (class "Default")
      (node (ref "PCB2") (pin "20") (pinfunction "20(SDA)_20") (pintype "bidirectional"))
    )
    (net (code "90") (name "unconnected-(PCB2-21(SCL)-Pad21)") (class "Default")
      (node (ref "PCB2") (pin "21") (pinfunction "21(SCL)_21") (pintype "bidirectional"))
    )
    (net (code "91") (name "unconnected-(PCB2-IOREF-PadI{slash}OREF)") (class "Default")
      (node (ref "PCB2") (pin "I/OREF") (pinfunction "IOREF_I/OREF") (pintype "bidirectional"))
    )
    (net (code "92") (name "unconnected-(PCB2-Pad+5V_)") (class "Default")
      (node (ref "PCB2") (pin "+5V_") (pinfunction "+5V__+5V_") (pintype "bidirectional"))
    )
    (net (code "93") (name "unconnected-(PCB2-Pad3.3V)") (class "Default")
      (node (ref "PCB2") (pin "3.3V") (pinfunction "3.3V_3.3V") (pintype "bidirectional"))
    )
    (net (code "94") (name "unconnected-(PCB2-Pad5)") (class "Default")
      (node (ref "PCB2") (pin "5") (pinfunction "5_5") (pintype "bidirectional"))
    )
    (net (code "95") (name "unconnected-(PCB2-Pad5V)") (class "Default")
      (node (ref "PCB2") (pin "5V") (pinfunction "5V_5V") (pintype "bidirectional"))
    )
    (net (code "96") (name "unconnected-(PCB2-Pad6)") (class "Default")
      (node (ref "PCB2") (pin "6") (pinfunction "6_6") (pintype "bidirectional"))
    )
    (net (code "97") (name "unconnected-(PCB2-Pad7)") (class "Default")
      (node (ref "PCB2") (pin "7") (pinfunction "7_7") (pintype "bidirectional"))
    )
    (net (code "98") (name "unconnected-(PCB2-Pad8)") (class "Default")
      (node (ref "PCB2") (pin "8") (pinfunction "8_8") (pintype "bidirectional"))
    )
    (net (code "99") (name "unconnected-(PCB2-Pad9)") (class "Default")
      (node (ref "PCB2") (pin "9") (pinfunction "9_9") (pintype "bidirectional"))
    )
    (net (code "100") (name "unconnected-(PCB2-Pad10)") (class "Default")
      (node (ref "PCB2") (pin "10") (pinfunction "10_10") (pintype "bidirectional"))
    )
    (net (code "101") (name "unconnected-(PCB2-Pad11)") (class "Default")
      (node (ref "PCB2") (pin "11") (pinfunction "11_11") (pintype "bidirectional"))
    )
    (net (code "102") (name "unconnected-(PCB2-Pad12)") (class "Default")
      (node (ref "PCB2") (pin "12") (pinfunction "12_12") (pintype "bidirectional"))
    )
    (net (code "103") (name "unconnected-(PCB2-Pad13)") (class "Default")
      (node (ref "PCB2") (pin "13") (pinfunction "13_13") (pintype "bidirectional"))
    )
    (net (code "104") (name "unconnected-(PCB2-Pad28)") (class "Default")
      (node (ref "PCB2") (pin "28") (pinfunction "28_28") (pintype "bidirectional"))
    )
    (net (code "105") (name "unconnected-(PCB2-Pad33)") (class "Default")
      (node (ref "PCB2") (pin "33") (pinfunction "33_33") (pintype "bidirectional"))
    )
    (net (code "106") (name "unconnected-(PCB2-Pad35)") (class "Default")
      (node (ref "PCB2") (pin "35") (pinfunction "35_35") (pintype "bidirectional"))
    )
    (net (code "107") (name "unconnected-(PCB2-Pad37)") (class "Default")
      (node (ref "PCB2") (pin "37") (pinfunction "37_37") (pintype "bidirectional"))
    )
    (net (code "108") (name "unconnected-(PCB2-Pad39)") (class "Default")
      (node (ref "PCB2") (pin "39") (pinfunction "39_39") (pintype "bidirectional"))
    )
    (net (code "109") (name "unconnected-(PCB2-Pad41)") (class "Default")
      (node (ref "PCB2") (pin "41") (pinfunction "41_41") (pintype "bidirectional"))
    )
    (net (code "110") (name "unconnected-(PCB2-Pad43)") (class "Default")
      (node (ref "PCB2") (pin "43") (pinfunction "43_43") (pintype "bidirectional"))
    )
    (net (code "111") (name "unconnected-(PCB2-Pad45)") (class "Default")
      (node (ref "PCB2") (pin "45") (pinfunction "45_45") (pintype "bidirectional"))
    )
    (net (code "112") (name "unconnected-(PCB2-Pad47)") (class "Default")
      (node (ref "PCB2") (pin "47") (pinfunction "47_47") (pintype "bidirectional"))
    )
    (net (code "113") (name "unconnected-(PCB2-Pad50)") (class "Default")
      (node (ref "PCB2") (pin "50") (pinfunction "50_50") (pintype "bidirectional"))
    )
    (net (code "114") (name "unconnected-(PCB2-Pad51)") (class "Default")
      (node (ref "PCB2") (pin "51") (pinfunction "51_51") (pintype "bidirectional"))
    )
    (net (code "115") (name "unconnected-(PCB2-Pad52)") (class "Default")
      (node (ref "PCB2") (pin "52") (pinfunction "52_52") (pintype "bidirectional"))
    )
    (net (code "116") (name "unconnected-(PCB2-Pad53)") (class "Default")
      (node (ref "PCB2") (pin "53") (pinfunction "53_53") (pintype "bidirectional"))
    )
    (net (code "117") (name "unconnected-(PCB2-PadA0)") (class "Default")
      (node (ref "PCB2") (pin "A0") (pinfunction "A0_A0") (pintype "bidirectional"))
    )
    (net (code "118") (name "unconnected-(PCB2-PadA1)") (class "Default")
      (node (ref "PCB2") (pin "A1") (pinfunction "A1_A1") (pintype "bidirectional"))
    )
    (net (code "119") (name "unconnected-(PCB2-PadA2)") (class "Default")
      (node (ref "PCB2") (pin "A2") (pinfunction "A2_A2") (pintype "bidirectional"))
    )
    (net (code "120") (name "unconnected-(PCB2-PadA3)") (class "Default")
      (node (ref "PCB2") (pin "A3") (pinfunction "A3_A3") (pintype "bidirectional"))
    )
    (net (code "121") (name "unconnected-(PCB2-PadA4)") (class "Default")
      (node (ref "PCB2") (pin "A4") (pinfunction "A4_A4") (pintype "bidirectional"))
    )
    (net (code "122") (name "unconnected-(PCB2-PadA5)") (class "Default")
      (node (ref "PCB2") (pin "A5") (pinfunction "A5_A5") (pintype "bidirectional"))
    )
    (net (code "123") (name "unconnected-(PCB2-PadA6)") (class "Default")
      (node (ref "PCB2") (pin "A6") (pinfunction "A6_A6") (pintype "bidirectional"))
    )
    (net (code "124") (name "unconnected-(PCB2-PadA7)") (class "Default")
      (node (ref "PCB2") (pin "A7") (pinfunction "A7_A7") (pintype "bidirectional"))
    )
    (net (code "125") (name "unconnected-(PCB2-PadA8)") (class "Default")
      (node (ref "PCB2") (pin "A8") (pinfunction "A8_A8") (pintype "bidirectional"))
    )
    (net (code "126") (name "unconnected-(PCB2-PadA9)") (class "Default")
      (node (ref "PCB2") (pin "A9") (pinfunction "A9_A9") (pintype "bidirectional"))
    )
    (net (code "127") (name "unconnected-(PCB2-PadA10)") (class "Default")
      (node (ref "PCB2") (pin "A10") (pinfunction "A10_A10") (pintype "bidirectional"))
    )
    (net (code "128") (name "unconnected-(PCB2-PadA11)") (class "Default")
      (node (ref "PCB2") (pin "A11") (pinfunction "A11_A11") (pintype "bidirectional"))
    )
    (net (code "129") (name "unconnected-(PCB2-PadA12)") (class "Default")
      (node (ref "PCB2") (pin "A12") (pinfunction "A12_A12") (pintype "bidirectional"))
    )
    (net (code "130") (name "unconnected-(PCB2-PadA13)") (class "Default")
      (node (ref "PCB2") (pin "A13") (pinfunction "A13_A13") (pintype "bidirectional"))
    )
    (net (code "131") (name "unconnected-(PCB2-PadA14)") (class "Default")
      (node (ref "PCB2") (pin "A14") (pinfunction "A14_A14") (pintype "bidirectional"))
    )
    (net (code "132") (name "unconnected-(PCB2-PadA15)") (class "Default")
      (node (ref "PCB2") (pin "A15") (pinfunction "A15_A15") (pintype "bidirectional"))
    )
    (net (code "133") (name "unconnected-(PCB2-PadGND.)") (class "Default")
      (node (ref "PCB2") (pin "GND.") (pinfunction "GND._GND.") (pintype "bidirectional"))
    )
    (net (code "134") (name "unconnected-(PCB2-PadGND..)") (class "Default")
      (node (ref "PCB2") (pin "GND..") (pinfunction "GND.._GND..") (pintype "bidirectional"))
    )
    (net (code "135") (name "unconnected-(PCB2-PadGND...)") (class "Default")
      (node (ref "PCB2") (pin "GND...") (pinfunction "GND..._GND...") (pintype "bidirectional"))
    )
    (net (code "136") (name "unconnected-(PCB2-PadGND....)") (class "Default")
      (node (ref "PCB2") (pin "GND....") (pinfunction "GND...._GND....") (pintype "bidirectional"))
    )
    (net (code "137") (name "unconnected-(PCB2-PadGND__)") (class "Default")
      (node (ref "PCB2") (pin "GND__") (pinfunction "GND___GND__") (pintype "bidirectional"))
    )
    (net (code "138") (name "unconnected-(PCB2-PadMISO)") (class "Default")
      (node (ref "PCB2") (pin "MISO") (pinfunction "MISO_MISO") (pintype "bidirectional"))
    )
    (net (code "139") (name "unconnected-(PCB2-PadMOSI)") (class "Default")
      (node (ref "PCB2") (pin "MOSI") (pinfunction "MOSI_MOSI") (pintype "bidirectional"))
    )
    (net (code "140") (name "unconnected-(PCB2-PadRESET)") (class "Default")
      (node (ref "PCB2") (pin "RESET") (pinfunction "RESET_RESET") (pintype "bidirectional"))
    )
    (net (code "141") (name "unconnected-(PCB2-PadRESET.)") (class "Default")
      (node (ref "PCB2") (pin "RESET.") (pinfunction "RESET._RESET.") (pintype "bidirectional"))
    )
    (net (code "142") (name "unconnected-(PCB2-PadSCK)") (class "Default")
      (node (ref "PCB2") (pin "SCK") (pinfunction "SCK_SCK") (pintype "bidirectional"))
    )
    (net (code "143") (name "unconnected-(PCB2-PadSCL1)") (class "Default")
      (node (ref "PCB2") (pin "SCL1") (pinfunction "SCL1_SCL1") (pintype "bidirectional"))
    )
    (net (code "144") (name "unconnected-(PCB2-PadSDA1)") (class "Default")
      (node (ref "PCB2") (pin "SDA1") (pinfunction "SDA1_SDA1") (pintype "bidirectional"))
    )
  )
)
